# Bridge_Switching.net
KiCad netlist of a schematic drawn in Altium Designer
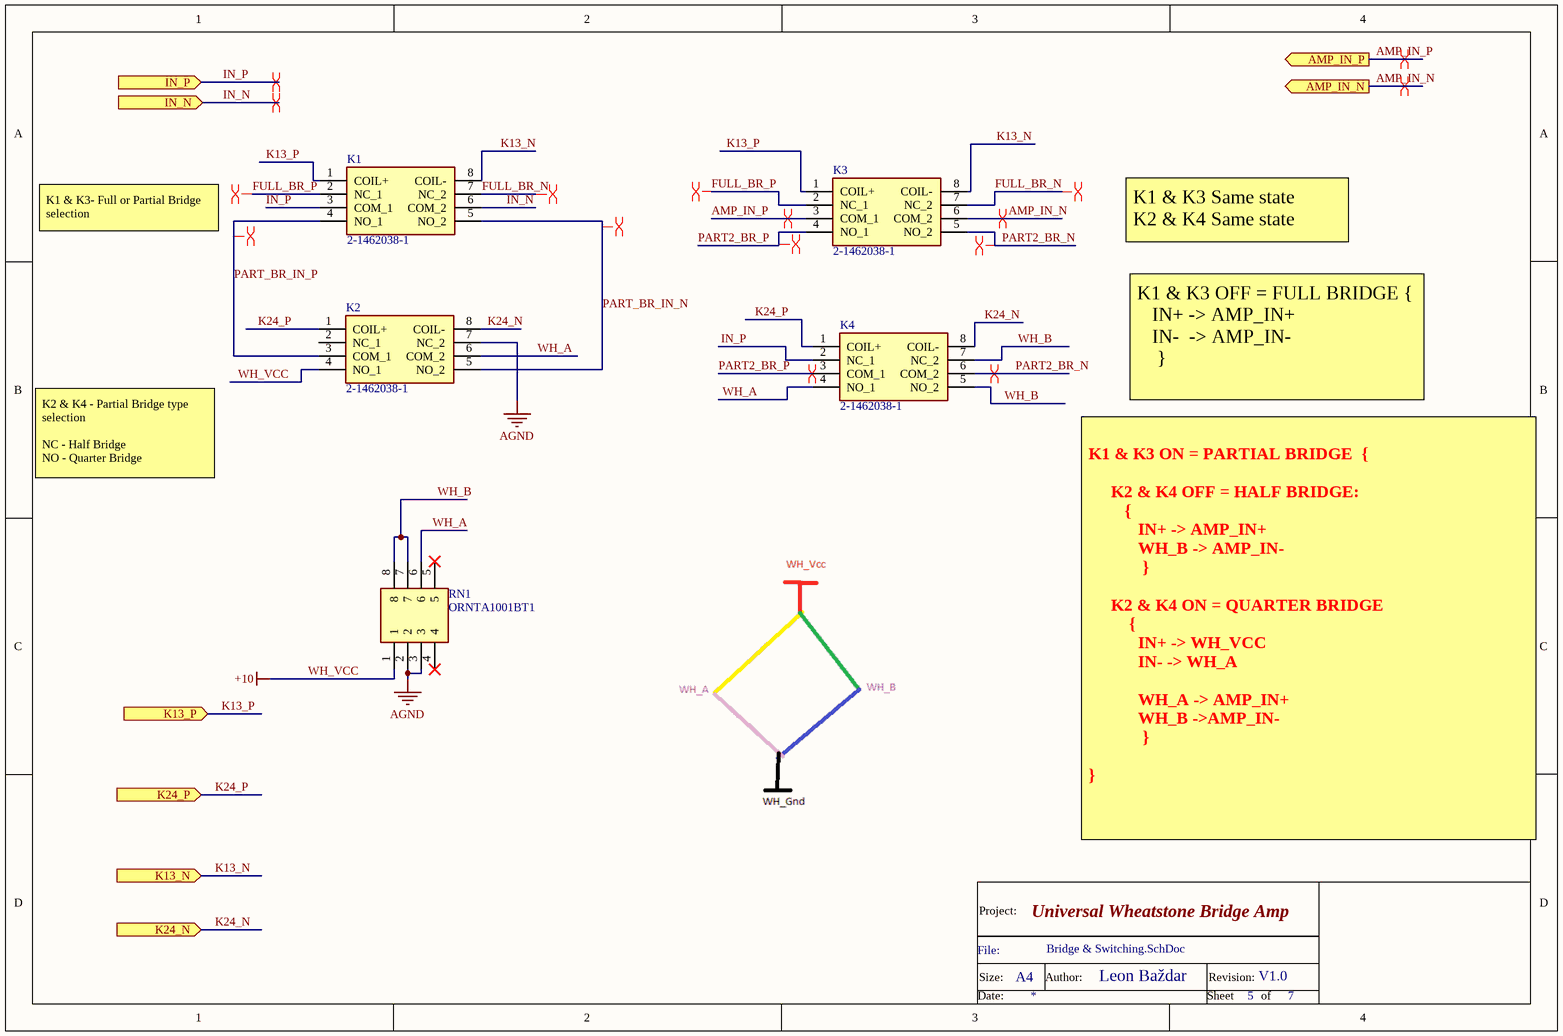
[diagram p0: Bridge & Switching.SchDoc]

(export (version "E")
  (design (tool "Eeschema 10.0.6"))
  (components
    (comp (ref "K1")
      (value "2-1462038-1")
      (footprint "SamacSys:214620381")
      (description "Relay or Contactor")
      (libsource (lib "*") (part "2-1462038-1"))
    )
    (comp (ref "K2")
      (value "2-1462038-1")
      (footprint "SamacSys:214620381")
      (description "Relay or Contactor")
      (libsource (lib "*") (part "2-1462038-1"))
    )
    (comp (ref "K3")
      (value "2-1462038-1")
      (footprint "SamacSys:214620381")
      (description "Relay or Contactor")
      (libsource (lib "*") (part "2-1462038-1"))
    )
    (comp (ref "K4")
      (value "2-1462038-1")
      (footprint "SamacSys:214620381")
      (description "Relay or Contactor")
      (libsource (lib "*") (part "2-1462038-1"))
    )
    (comp (ref "RN1")
      (value "ORNTA1001BT1")
      (footprint "SamacSys:SOIC127P607X173-8N")
      (description "Resistor Network")
      (fields (field (name "MOUSER PART NUMBER") "71-ORNTA1001BT1"))
      (libsource (lib "*") (part "ORNTA1001BT1"))
    )
  )
  (nets
    (net (code "1") (name "+10") (class "Default")
      (node (ref "K2") (pin "4") (pinfunction "NO_1_4") (pintype "passive"))
      (node (ref "RN1") (pin "1") (pinfunction "1_1") (pintype "passive"))
    )
    (net (code "2") (name "/AMP_IN_N") (class "Default")
      (node (ref "K3") (pin "6") (pinfunction "COM_2_6") (pintype "passive"))
    )
    (net (code "3") (name "/AMP_IN_P") (class "Default")
      (node (ref "K3") (pin "3") (pinfunction "COM_1_3") (pintype "passive"))
    )
    (net (code "4") (name "/FULL_BR_N") (class "Default")
      (node (ref "K1") (pin "7") (pinfunction "NC_2_7") (pintype "passive"))
      (node (ref "K3") (pin "7") (pinfunction "NC_2_7") (pintype "passive"))
    )
    (net (code "5") (name "/FULL_BR_P") (class "Default")
      (node (ref "K1") (pin "2") (pinfunction "NC_1_2") (pintype "passive"))
      (node (ref "K3") (pin "2") (pinfunction "NC_1_2") (pintype "passive"))
    )
    (net (code "6") (name "/IN_N") (class "Default")
      (node (ref "K1") (pin "6") (pinfunction "COM_2_6") (pintype "passive"))
    )
    (net (code "7") (name "/IN_P") (class "Default")
      (node (ref "K1") (pin "3") (pinfunction "COM_1_3") (pintype "passive"))
      (node (ref "K4") (pin "2") (pinfunction "NC_1_2") (pintype "passive"))
    )
    (net (code "8") (name "/K13_N") (class "Default")
      (node (ref "K1") (pin "8") (pinfunction "COIL-_8") (pintype "passive"))
      (node (ref "K3") (pin "8") (pinfunction "COIL-_8") (pintype "passive"))
    )
    (net (code "9") (name "/K13_P") (class "Default")
      (node (ref "K1") (pin "1") (pinfunction "COIL+_1") (pintype "passive"))
      (node (ref "K3") (pin "1") (pinfunction "COIL+_1") (pintype "passive"))
    )
    (net (code "10") (name "/K24_N") (class "Default")
      (node (ref "K2") (pin "8") (pinfunction "COIL-_8") (pintype "passive"))
      (node (ref "K4") (pin "8") (pinfunction "COIL-_8") (pintype "passive"))
    )
    (net (code "11") (name "/K24_P") (class "Default")
      (node (ref "K2") (pin "1") (pinfunction "COIL+_1") (pintype "passive"))
      (node (ref "K4") (pin "1") (pinfunction "COIL+_1") (pintype "passive"))
    )
    (net (code "12") (name "/PART2_BR_N") (class "Default")
      (node (ref "K3") (pin "5") (pinfunction "NO_2_5") (pintype "passive"))
      (node (ref "K4") (pin "6") (pinfunction "COM_2_6") (pintype "passive"))
    )
    (net (code "13") (name "/PART2_BR_P") (class "Default")
      (node (ref "K3") (pin "4") (pinfunction "NO_1_4") (pintype "passive"))
      (node (ref "K4") (pin "3") (pinfunction "COM_1_3") (pintype "passive"))
    )
    (net (code "14") (name "/PART_BR_IN_N") (class "Default")
      (node (ref "K1") (pin "5") (pinfunction "NO_2_5") (pintype "passive"))
      (node (ref "K2") (pin "5") (pinfunction "NO_2_5") (pintype "passive"))
    )
    (net (code "15") (name "/PART_BR_IN_P") (class "Default")
      (node (ref "K1") (pin "4") (pinfunction "NO_1_4") (pintype "passive"))
      (node (ref "K2") (pin "3") (pinfunction "COM_1_3") (pintype "passive"))
    )
    (net (code "16") (name "/WH_A") (class "Default")
      (node (ref "K2") (pin "6") (pinfunction "COM_2_6") (pintype "passive"))
      (node (ref "K4") (pin "4") (pinfunction "NO_1_4") (pintype "passive"))
      (node (ref "RN1") (pin "6") (pinfunction "6_6") (pintype "passive"))
    )
    (net (code "17") (name "/WH_B") (class "Default")
      (node (ref "K4") (pin "5") (pinfunction "NO_2_5") (pintype "passive"))
      (node (ref "K4") (pin "7") (pinfunction "NC_2_7") (pintype "passive"))
      (node (ref "RN1") (pin "7") (pinfunction "7_7") (pintype "passive"))
      (node (ref "RN1") (pin "8") (pinfunction "8_8") (pintype "passive"))
    )
    (net (code "18") (name "AGND") (class "Default")
      (node (ref "K2") (pin "7") (pinfunction "NC_2_7") (pintype "passive"))
      (node (ref "RN1") (pin "2") (pinfunction "2_2") (pintype "passive"))
      (node (ref "RN1") (pin "3") (pinfunction "3_3") (pintype "passive"))
    )
    (net (code "19") (name "unconnected-(K2-NC_1-Pad2)") (class "Default")
      (node (ref "K2") (pin "2") (pinfunction "NC_1_2") (pintype "passive"))
    )
    (net (code "20") (name "unconnected-(RN1-Pad4)") (class "Default")
      (node (ref "RN1") (pin "4") (pinfunction "4_4") (pintype "passive+no_connect"))
    )
    (net (code "21") (name "unconnected-(RN1-Pad5)") (class "Default")
      (node (ref "RN1") (pin "5") (pinfunction "5_5") (pintype "passive+no_connect"))
    )
  )
)
